# RTU_LMG_Linear_Voltage_Regulator_3V3.net
KiCad netlist of a schematic drawn in Altium Designer
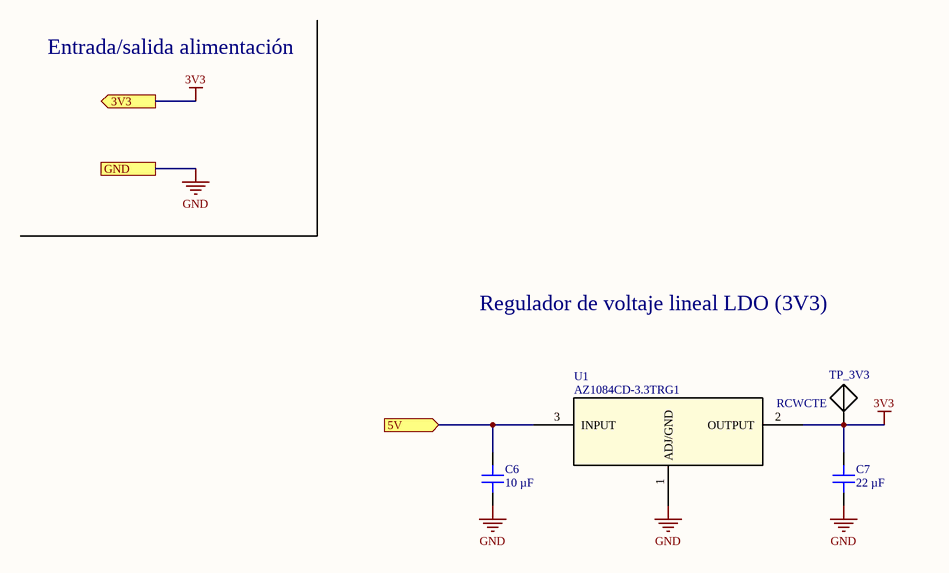
[diagram p0: RTU_LMG_Linear_Voltage_Regulator_3V3.SchDoc]

(export (version "E")
  (design (tool "Eeschema 10.0.6"))
  (components
    (comp (ref "C6")
      (value "10 µF")
      (footprint "PCB - CAPACITOR - MLCC - CAP 1210_3225 - 1MM:CAP 1210_3225 - 1MM")
      (description "CAP CER 10UF 75V X7R 1210")
      (fields
        (field (name "PART NUMBER") "C3225X7R1N106K250AC")
        (field (name "MANUFACTURER") "TDK Corporation")
      )
      (libsource (lib "Celestial Altium Library - altium_library") (part "Capacitor"))
    )
    (comp (ref "C7")
      (value "22 µF")
      (footprint "PCB - CAPACITOR - MLCC - CAP 0805_2012:CAP 0805_2012")
      (description "CAP CER 22UF 16V X5R 0805")
      (fields
        (field (name "PART NUMBER") "CL21A226MOCLRNC")
        (field (name "MANUFACTURER") "Samsung Electro-Mechanics")
      )
      (libsource (lib "Celestial Altium Library - altium_library") (part "Capacitor"))
    )
    (comp (ref "TP_3V3")
      (value "RCWCTE")
      (footprint "RCWCTE")
      (description "- PC Test Point - - Plating Surface Mount Mounting Type")
      (fields (field (name "MF") "KOA Speer") (field (name "DIGI-KEY_PART_NUMBER") "2019-RCWCTETR-ND"))
      (libsource (lib "DIN_DC_Base_Board_components") (part "RCWCTE"))
    )
    (comp (ref "U1")
      (value "AZ1084CD-3.3TRG1")
      (footprint "TO252-3")
      (description "Fuente regulada LDO - 3V3 - 5A")
      (fields (field (name "COPYRIGHT") "Copyright (C) 2023 Ultra Librarian. All rights reserved."))
      (libsource (lib "DIN_DC_Base_Board_components_SCH_footprints") (part "AZ1084CD-3.3TRG1"))
    )
  )
  (nets
    (net (code "1") (name "/5V") (class "Default")
      (node (ref "C6") (pin "1") (pinfunction "1_1") (pintype "passive"))
      (node (ref "U1") (pin "3") (pinfunction "INPUT_3") (pintype "passive"))
    )
    (net (code "2") (name "3V3") (class "Default")
      (node (ref "C7") (pin "2") (pinfunction "2_2") (pintype "passive"))
      (node (ref "TP_3V3") (pin "1") (pinfunction "TP_1") (pintype "passive"))
      (node (ref "U1") (pin "2") (pinfunction "OUTPUT_2") (pintype "passive"))
    )
    (net (code "3") (name "GND") (class "Default")
      (node (ref "C6") (pin "2") (pinfunction "2_2") (pintype "passive"))
      (node (ref "C7") (pin "1") (pinfunction "1_1") (pintype "passive"))
      (node (ref "U1") (pin "1") (pinfunction "ADJ/GND_1") (pintype "power_in"))
    )
  )
)
